# SML-230109PCB2__NFC.net
KiCad netlist of a schematic drawn in Altium Designer
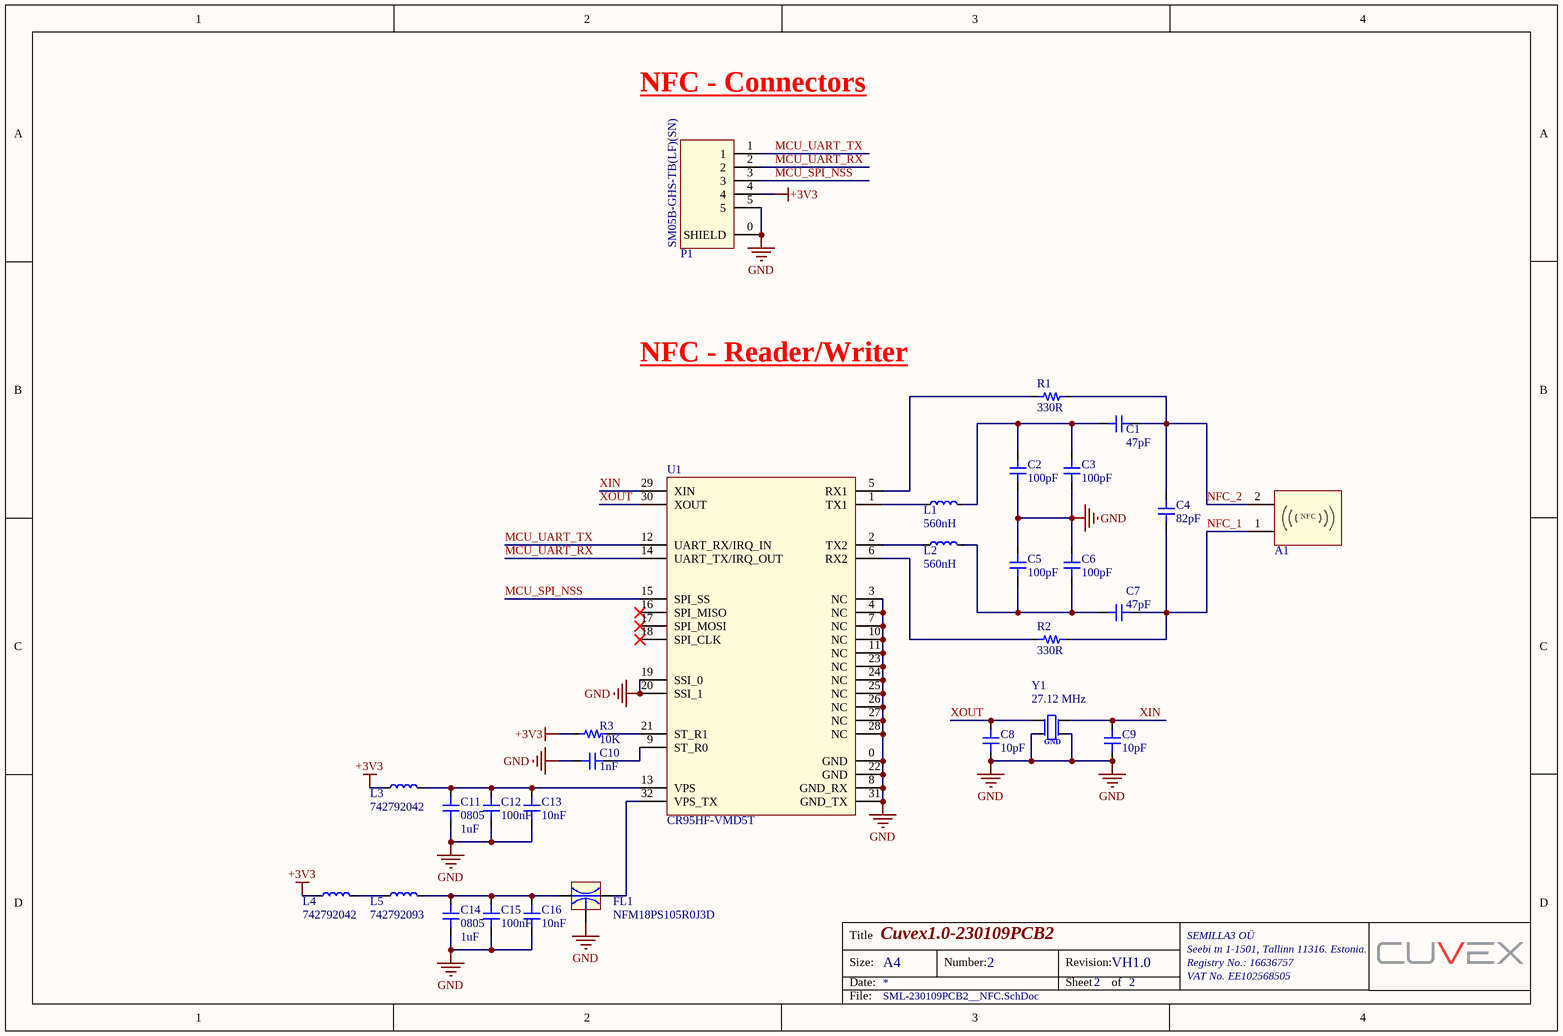
[diagram p0: SML-230109PCB2__NFC.SchDoc]

(export (version "E")
  (design (tool "Eeschema 10.0.6"))
  (components
    (comp (ref "A1")
      (value ".")
      (footprint "ANT-PCB__NFC-MODEL-1")
      (description "ANTENNA PCB, NFC, model 1")
      (libsource (lib "DEB_LIB_SCH_22-03") (part "ANT-PCB__NFC-MODEL-1"))
    )
    (comp (ref "C1")
      (value "47pF")
      (footprint "[G] CAP-MLCC__0603")
      (description "CAP MLCC 0603")
      (fields (field (name "VOLTAGE") "010") (field (name "Comment") "."))
      (libsource (lib "DEB_LIB_SCH_22-03") (part "CAP_MLCC_0603"))
    )
    (comp (ref "C2")
      (value "100pF")
      (footprint "[G] CAP-MLCC__0603")
      (description "CAP MLCC 0603")
      (fields (field (name "VOLTAGE") "010") (field (name "Comment") "."))
      (libsource (lib "DEB_LIB_SCH_22-03") (part "CAP_MLCC_0603"))
    )
    (comp (ref "C3")
      (value "100pF")
      (footprint "[G] CAP-MLCC__0603")
      (description "CAP MLCC 0603")
      (fields (field (name "VOLTAGE") "010") (field (name "Comment") "."))
      (libsource (lib "DEB_LIB_SCH_22-03") (part "CAP_MLCC_0603"))
    )
    (comp (ref "C4")
      (value "82pF")
      (footprint "[G] CAP-MLCC__0603")
      (description "CAP MLCC 0603")
      (fields (field (name "VOLTAGE") "010") (field (name "Comment") "."))
      (libsource (lib "DEB_LIB_SCH_22-03") (part "CAP_MLCC_0603"))
    )
    (comp (ref "C5")
      (value "100pF")
      (footprint "[G] CAP-MLCC__0603")
      (description "CAP MLCC 0603")
      (fields (field (name "VOLTAGE") "010") (field (name "Comment") "."))
      (libsource (lib "DEB_LIB_SCH_22-03") (part "CAP_MLCC_0603"))
    )
    (comp (ref "C6")
      (value "100pF")
      (footprint "[G] CAP-MLCC__0603")
      (description "CAP MLCC 0603")
      (fields (field (name "VOLTAGE") "010") (field (name "Comment") "."))
      (libsource (lib "DEB_LIB_SCH_22-03") (part "CAP_MLCC_0603"))
    )
    (comp (ref "C7")
      (value "47pF")
      (footprint "[G] CAP-MLCC__0603")
      (description "CAP MLCC 0603")
      (fields (field (name "VOLTAGE") "010") (field (name "Comment") "."))
      (libsource (lib "DEB_LIB_SCH_22-03") (part "CAP_MLCC_0603"))
    )
    (comp (ref "C8")
      (value "10pF")
      (footprint "[G] CAP-MLCC__0603")
      (description "CAP MLCC 0603")
      (fields (field (name "VOLTAGE") "010") (field (name "Comment") "."))
      (libsource (lib "DEB_LIB_SCH_22-03") (part "CAP_MLCC_0603"))
    )
    (comp (ref "C9")
      (value "10pF")
      (footprint "[G] CAP-MLCC__0603")
      (description "CAP MLCC 0603")
      (fields (field (name "VOLTAGE") "010") (field (name "Comment") "."))
      (libsource (lib "DEB_LIB_SCH_22-03") (part "CAP_MLCC_0603"))
    )
    (comp (ref "C10")
      (value "1nF")
      (footprint "[G] CAP-MLCC__0603")
      (description "CAP MLCC 0603")
      (fields (field (name "VOLTAGE") "010") (field (name "Comment") "."))
      (libsource (lib "DEB_LIB_SCH_22-03") (part "CAP_MLCC_0603"))
    )
    (comp (ref "C11")
      (value "1uF")
      (footprint "[G] CAP-MLCC__0805")
      (description "CAP MLCC 0805")
      (fields
        (field (name "VOLTAGE") "010")
        (field (name "[06] - PACKAGE") "0805")
        (field (name "Comment") ".")
      )
      (libsource (lib "DEB_LIB_SCH_22-03") (part "CAP_MLCC_0805"))
    )
    (comp (ref "C12")
      (value "100nF")
      (footprint "[G] CAP-MLCC__0603")
      (description "CAP MLCC 0603")
      (fields (field (name "VOLTAGE") "010") (field (name "Comment") "."))
      (libsource (lib "DEB_LIB_SCH_22-03") (part "CAP_MLCC_0603"))
    )
    (comp (ref "C13")
      (value "10nF")
      (footprint "[G] CAP-MLCC__0603")
      (description "CAP MLCC 0603")
      (fields (field (name "VOLTAGE") "010") (field (name "Comment") "."))
      (libsource (lib "DEB_LIB_SCH_22-03") (part "CAP_MLCC_0603"))
    )
    (comp (ref "C14")
      (value "1uF")
      (footprint "[G] CAP-MLCC__0805")
      (description "CAP MLCC 0805")
      (fields
        (field (name "VOLTAGE") "010")
        (field (name "[06] - PACKAGE") "0805")
        (field (name "Comment") ".")
      )
      (libsource (lib "DEB_LIB_SCH_22-03") (part "CAP_MLCC_0805"))
    )
    (comp (ref "C15")
      (value "100nF")
      (footprint "[G] CAP-MLCC__0603")
      (description "CAP MLCC 0603")
      (fields (field (name "VOLTAGE") "010") (field (name "Comment") "."))
      (libsource (lib "DEB_LIB_SCH_22-03") (part "CAP_MLCC_0603"))
    )
    (comp (ref "C16")
      (value "10nF")
      (footprint "[G] CAP-MLCC__0603")
      (description "CAP MLCC 0603")
      (fields (field (name "VOLTAGE") "010") (field (name "Comment") "."))
      (libsource (lib "DEB_LIB_SCH_22-03") (part "CAP_MLCC_0603"))
    )
    (comp (ref "FL1")
      (value ".")
      (footprint "EMIFIL-0603__NFM18PS")
      (description "EMIFIL 0603, Murata, NFM18PS, 1uF, 6'3V, 2A")
      (fields (field (name "[01] - MPN CODE") "NFM18PS105R0J3D"))
      (libsource (lib "DEB_LIB_SCH_22-03") (part "NFM18PS105R0J3D"))
    )
    (comp (ref "L1")
      (value "560nH")
      (footprint "[G] IND__0805")
      (description "IND SMD 0805 [G]")
      (fields (field (name "Comment") "."))
      (libsource (lib "DEB_LIB_SCH_22-03") (part "IND_SMD_0805"))
    )
    (comp (ref "L2")
      (value "560nH")
      (footprint "[G] IND__0805")
      (description "IND SMD 0805 [G]")
      (fields (field (name "Comment") "."))
      (libsource (lib "DEB_LIB_SCH_22-03") (part "IND_SMD_0805"))
    )
    (comp (ref "L3")
      (value ".")
      (footprint "[G] IND__0805")
      (description "IND SMD 0805 [G]")
      (fields (field (name "[01] - MPN CODE") "742792042"))
      (libsource (lib "DEB_LIB_SCH_22-03") (part "IND_SMD_0805"))
    )
    (comp (ref "L4")
      (value ".")
      (footprint "[G] IND__0805")
      (description "IND SMD 0805 [G]")
      (fields (field (name "[01] - MPN CODE") "742792042"))
      (libsource (lib "DEB_LIB_SCH_22-03") (part "IND_SMD_0805"))
    )
    (comp (ref "L5")
      (value ".")
      (footprint "[G] IND__0805")
      (description "IND SMD 0805 [G]")
      (fields (field (name "[01] - MPN CODE") "742792093"))
      (libsource (lib "DEB_LIB_SCH_22-03") (part "IND_SMD_0805"))
    )
    (comp (ref "P1")
      (value ".")
      (footprint "CONN-SMD__JST(5PIN)__SM05B-GHS-TB(LF)(SN)")
      (description "CONN SMD, JST, side entry, 1x5pin, with lock, 1A, 50V")
      (fields (field (name "[01] - MPN CODE") "SM05B-GHS-TB(LF)(SN)"))
      (libsource (lib "DEB_LIB_SCH_22-03") (part "SM05B-GHS-TB(LF)(SN)"))
    )
    (comp (ref "R1")
      (value "330R")
      (footprint "[G] RES-CHIP__0603")
      (description "RES SMD 0603 [G]")
      (fields (field (name "TOLERANCE") "1%") (field (name "Comment") "."))
      (libsource (lib "DEB_LIB_SCH_22-03") (part "RES_SMD_0603"))
    )
    (comp (ref "R2")
      (value "330R")
      (footprint "[G] RES-CHIP__0603")
      (description "RES SMD 0603 [G]")
      (fields (field (name "TOLERANCE") "1%") (field (name "Comment") "."))
      (libsource (lib "DEB_LIB_SCH_22-03") (part "RES_SMD_0603"))
    )
    (comp (ref "R3")
      (value "10K")
      (footprint "[G] RES-CHIP__0603")
      (description "RES SMD 0603 [G]")
      (fields (field (name "TOLERANCE") "1%") (field (name "Comment") "."))
      (libsource (lib "DEB_LIB_SCH_22-03") (part "RES_SMD_0603"))
    )
    (comp (ref "U1")
      (value "CR95HF-VMD5T")
      (footprint "IC-NFC-RDR/WTR__CR95HF__VFQFPN32")
      (description "IC NFC READER/WRITER, SPI/UART, 13'56 MHz, Vdd=2'7-3'3V")
      (fields (field (name "[01] - MPN CODE") "CR95HF-VMD5T"))
      (libsource (lib "DEB_LIB_SCH_22-03") (part "CR95HF-VMD5T"))
    )
    (comp (ref "Y1")
      (value "27.12 MHz")
      (footprint "CRYSTAL__ABM8G")
      (description "CRYSTAL, 27.1200MHz, ±10ppm, CL=10pF, CS=5pF")
      (fields (field (name "Comment") "."))
      (libsource (lib "DEB_LIB_SCH_22-03") (part "ABM8G-27.120MHZ-10-D1-T"))
    )
  )
  (nets
    (net (code "1") (name "+3V3") (class "Default")
      (node (ref "L3") (pin "1") (pinfunction "1_1") (pintype "passive"))
      (node (ref "L4") (pin "1") (pinfunction "1_1") (pintype "passive"))
      (node (ref "P1") (pin "4") (pinfunction "4_4") (pintype "passive"))
      (node (ref "R3") (pin "1") (pinfunction "1_1") (pintype "passive"))
    )
    (net (code "2") (name "/MCU_SPI_NSS") (class "Default")
      (node (ref "P1") (pin "3") (pinfunction "3_3") (pintype "passive"))
      (node (ref "U1") (pin "15") (pinfunction "SPI_SS_15") (pintype "passive"))
    )
    (net (code "3") (name "/MCU_UART_RX") (class "Default")
      (node (ref "P1") (pin "2") (pinfunction "2_2") (pintype "passive"))
      (node (ref "U1") (pin "14") (pinfunction "UART_TX/IRQ_OUT_14") (pintype "passive"))
    )
    (net (code "4") (name "/MCU_UART_TX") (class "Default")
      (node (ref "P1") (pin "1") (pinfunction "1_1") (pintype "passive"))
      (node (ref "U1") (pin "12") (pinfunction "UART_RX/IRQ_IN_12") (pintype "passive"))
    )
    (net (code "5") (name "/NFC_1") (class "Default")
      (node (ref "A1") (pin "1") (pinfunction "1_1") (pintype "passive"))
      (node (ref "C4") (pin "1") (pinfunction "1_1") (pintype "passive"))
      (node (ref "C7") (pin "2") (pinfunction "2_2") (pintype "passive"))
      (node (ref "R2") (pin "2") (pinfunction "2_2") (pintype "passive"))
    )
    (net (code "6") (name "/NFC_2") (class "Default")
      (node (ref "A1") (pin "2") (pinfunction "2_2") (pintype "passive"))
      (node (ref "C1") (pin "2") (pinfunction "2_2") (pintype "passive"))
      (node (ref "C4") (pin "2") (pinfunction "2_2") (pintype "passive"))
      (node (ref "R1") (pin "2") (pinfunction "2_2") (pintype "passive"))
    )
    (net (code "7") (name "/XIN") (class "Default")
      (node (ref "C9") (pin "1") (pinfunction "1_1") (pintype "passive"))
      (node (ref "U1") (pin "29") (pinfunction "XIN_29") (pintype "passive"))
      (node (ref "Y1") (pin "3") (pinfunction "OSC2_3") (pintype "passive"))
    )
    (net (code "8") (name "/XOUT") (class "Default")
      (node (ref "C8") (pin "1") (pinfunction "1_1") (pintype "passive"))
      (node (ref "U1") (pin "30") (pinfunction "XOUT_30") (pintype "passive"))
      (node (ref "Y1") (pin "1") (pinfunction "OSC1_1") (pintype "passive"))
    )
    (net (code "9") (name "GND") (class "Default")
      (node (ref "C10") (pin "2") (pinfunction "2_2") (pintype "passive"))
      (node (ref "C11") (pin "1") (pinfunction "1_1") (pintype "passive"))
      (node (ref "C12") (pin "1") (pinfunction "1_1") (pintype "passive"))
      (node (ref "C13") (pin "1") (pinfunction "1_1") (pintype "passive"))
      (node (ref "C14") (pin "1") (pinfunction "1_1") (pintype "passive"))
      (node (ref "C15") (pin "1") (pinfunction "1_1") (pintype "passive"))
      (node (ref "C16") (pin "1") (pinfunction "1_1") (pintype "passive"))
      (node (ref "C2") (pin "1") (pinfunction "1_1") (pintype "passive"))
      (node (ref "C3") (pin "1") (pinfunction "1_1") (pintype "passive"))
      (node (ref "C5") (pin "2") (pinfunction "2_2") (pintype "passive"))
      (node (ref "C6") (pin "2") (pinfunction "2_2") (pintype "passive"))
      (node (ref "C8") (pin "2") (pinfunction "2_2") (pintype "passive"))
      (node (ref "C9") (pin "2") (pinfunction "2_2") (pintype "passive"))
      (node (ref "FL1") (pin "0") (pinfunction "0_0") (pintype "passive"))
      (node (ref "P1") (pin "0") (pinfunction "SHIELD_0") (pintype "passive"))
      (node (ref "P1") (pin "5") (pinfunction "5_5") (pintype "passive"))
      (node (ref "U1") (pin "0") (pinfunction "GND_0") (pintype "passive"))
      (node (ref "U1") (pin "10") (pinfunction "NC_10") (pintype "passive"))
      (node (ref "U1") (pin "11") (pinfunction "NC_11") (pintype "passive"))
      (node (ref "U1") (pin "19") (pinfunction "SSI_0_19") (pintype "passive"))
      (node (ref "U1") (pin "20") (pinfunction "SSI_1_20") (pintype "passive"))
      (node (ref "U1") (pin "22") (pinfunction "GND_22") (pintype "passive"))
      (node (ref "U1") (pin "23") (pinfunction "NC_23") (pintype "passive"))
      (node (ref "U1") (pin "24") (pinfunction "NC_24") (pintype "passive"))
      (node (ref "U1") (pin "25") (pinfunction "NC_25") (pintype "passive"))
      (node (ref "U1") (pin "26") (pinfunction "NC_26") (pintype "passive"))
      (node (ref "U1") (pin "27") (pinfunction "NC_27") (pintype "passive"))
      (node (ref "U1") (pin "28") (pinfunction "NC_28") (pintype "passive"))
      (node (ref "U1") (pin "3") (pinfunction "NC_3") (pintype "passive"))
      (node (ref "U1") (pin "31") (pinfunction "GND_TX_31") (pintype "passive"))
      (node (ref "U1") (pin "4") (pinfunction "NC_4") (pintype "passive"))
      (node (ref "U1") (pin "7") (pinfunction "NC_7") (pintype "passive"))
      (node (ref "U1") (pin "8") (pinfunction "GND_RX_8") (pintype "passive"))
      (node (ref "Y1") (pin "2") (pinfunction "gnd_2") (pintype "passive"))
      (node (ref "Y1") (pin "4") (pinfunction "gnd_4") (pintype "passive"))
    )
    (net (code "10") (name "Net-(C1-Pad1)") (class "Default")
      (node (ref "C1") (pin "1") (pinfunction "1_1") (pintype "passive"))
      (node (ref "C2") (pin "2") (pinfunction "2_2") (pintype "passive"))
      (node (ref "C3") (pin "2") (pinfunction "2_2") (pintype "passive"))
      (node (ref "L1") (pin "2") (pinfunction "2_2") (pintype "passive"))
    )
    (net (code "11") (name "Net-(C5-Pad1)") (class "Default")
      (node (ref "C5") (pin "1") (pinfunction "1_1") (pintype "passive"))
      (node (ref "C6") (pin "1") (pinfunction "1_1") (pintype "passive"))
      (node (ref "C7") (pin "1") (pinfunction "1_1") (pintype "passive"))
      (node (ref "L2") (pin "2") (pinfunction "2_2") (pintype "passive"))
    )
    (net (code "12") (name "Net-(C14-Pad2)") (class "Default")
      (node (ref "C14") (pin "2") (pinfunction "2_2") (pintype "passive"))
      (node (ref "C15") (pin "2") (pinfunction "2_2") (pintype "passive"))
      (node (ref "C16") (pin "2") (pinfunction "2_2") (pintype "passive"))
      (node (ref "FL1") (pin "1") (pinfunction "1_1") (pintype "passive"))
      (node (ref "L5") (pin "2") (pinfunction "2_2") (pintype "passive"))
    )
    (net (code "13") (name "Net-(L4-Pad2)") (class "Default")
      (node (ref "L4") (pin "2") (pinfunction "2_2") (pintype "passive"))
      (node (ref "L5") (pin "1") (pinfunction "1_1") (pintype "passive"))
    )
    (net (code "14") (name "Net-(U1-RX1)") (class "Default")
      (node (ref "R1") (pin "1") (pinfunction "1_1") (pintype "passive"))
      (node (ref "U1") (pin "5") (pinfunction "RX1_5") (pintype "passive"))
    )
    (net (code "15") (name "Net-(U1-RX2)") (class "Default")
      (node (ref "R2") (pin "1") (pinfunction "1_1") (pintype "passive"))
      (node (ref "U1") (pin "6") (pinfunction "RX2_6") (pintype "passive"))
    )
    (net (code "16") (name "Net-(U1-ST_R0)") (class "Default")
      (node (ref "C10") (pin "1") (pinfunction "1_1") (pintype "passive"))
      (node (ref "U1") (pin "9") (pinfunction "ST_R0_9") (pintype "passive"))
    )
    (net (code "17") (name "Net-(U1-ST_R1)") (class "Default")
      (node (ref "R3") (pin "2") (pinfunction "2_2") (pintype "passive"))
      (node (ref "U1") (pin "21") (pinfunction "ST_R1_21") (pintype "passive"))
    )
    (net (code "18") (name "Net-(U1-TX1)") (class "Default")
      (node (ref "L1") (pin "1") (pinfunction "1_1") (pintype "passive"))
      (node (ref "U1") (pin "1") (pinfunction "TX1_1") (pintype "passive"))
    )
    (net (code "19") (name "Net-(U1-TX2)") (class "Default")
      (node (ref "L2") (pin "1") (pinfunction "1_1") (pintype "passive"))
      (node (ref "U1") (pin "2") (pinfunction "TX2_2") (pintype "passive"))
    )
    (net (code "20") (name "Net-(U1-VPS)") (class "Default")
      (node (ref "C11") (pin "2") (pinfunction "2_2") (pintype "passive"))
      (node (ref "C12") (pin "2") (pinfunction "2_2") (pintype "passive"))
      (node (ref "C13") (pin "2") (pinfunction "2_2") (pintype "passive"))
      (node (ref "L3") (pin "2") (pinfunction "2_2") (pintype "passive"))
      (node (ref "U1") (pin "13") (pinfunction "VPS_13") (pintype "passive"))
    )
    (net (code "21") (name "Net-(U1-VPS_TX)") (class "Default")
      (node (ref "FL1") (pin "2") (pinfunction "2_2") (pintype "passive"))
      (node (ref "U1") (pin "32") (pinfunction "VPS_TX_32") (pintype "passive"))
    )
    (net (code "22") (name "unconnected-(U1-SPI_CLK-Pad18)") (class "Default")
      (node (ref "U1") (pin "18") (pinfunction "SPI_CLK_18") (pintype "passive+no_connect"))
    )
    (net (code "23") (name "unconnected-(U1-SPI_MISO-Pad16)") (class "Default")
      (node (ref "U1") (pin "16") (pinfunction "SPI_MISO_16") (pintype "passive+no_connect"))
    )
    (net (code "24") (name "unconnected-(U1-SPI_MOSI-Pad17)") (class "Default")
      (node (ref "U1") (pin "17") (pinfunction "SPI_MOSI_17") (pintype "passive+no_connect"))
    )
  )
)
